# Microcontroller_IO.net
KiCad netlist of a schematic drawn in Altium Designer
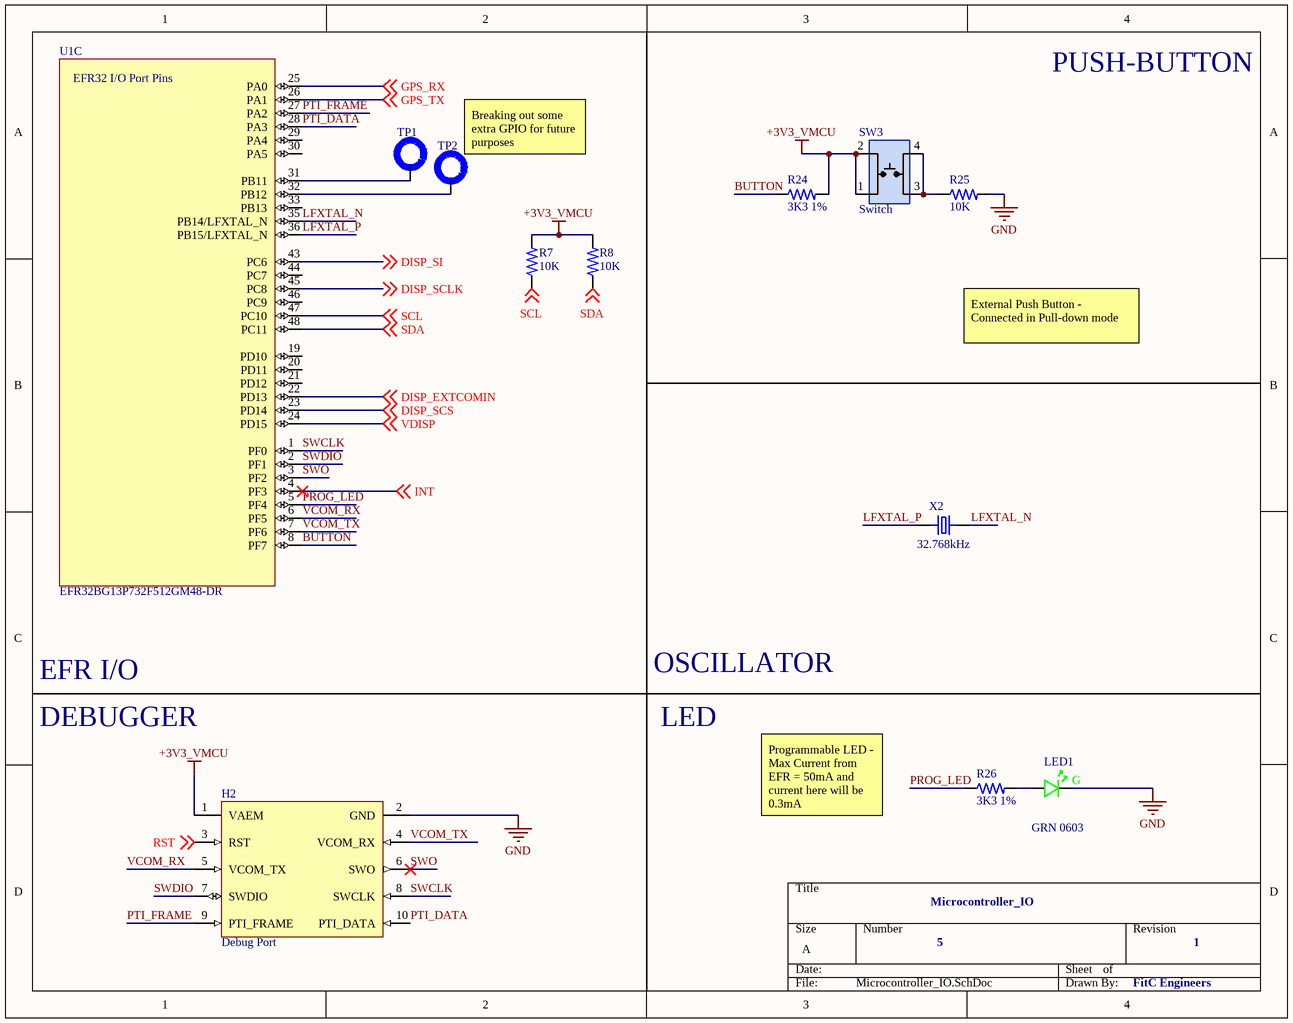
[diagram p0: Microcontroller_IO.SchDoc]

(export (version "E")
  (design (tool "Eeschema 10.0.6"))
  (components
    (comp (ref "H2")
      (value "Debug Port")
      (footprint "Amphenol_20021121_0")
      (description "CONN HEADER SMD 10POS 1.27MM. Connector Header Surface Mount 10 position 0.050\"")
      (fields
        (field (name "MANUFACTURER") "Amphenol ICC / FCI")
        (field (name "MANUFACTURER PART NUMBER") "20021121-00010C1LF")
      )
      (libsource (lib "LP_Project_Parts") (part "20021121-00010C1LF"))
    )
    (comp (ref "LED1")
      (value "GRN 0603")
      (footprint "LED_0603_GRN_WL-SMCW")
      (description "LED, 0603, GREEN, 430MCD, 520NM")
      (fields
        (field (name "MANUFACTURER") "Wurth Electronics")
        (field (name "MANUFACTURER PART NUMBER") "150060GS75000")
      )
      (libsource (lib "LP_Project_Parts") (part "150060GS75000"))
    )
    (comp (ref "R7")
      (value "10K")
      (footprint "RES_0603_1608X06")
      (description "Res Thin Film 0603 10K Ohm 1% 1/8W ±100ppm/°C Molded SMD SMD Paper T/R")
      (fields
        (field (name "MANUFACTURER") "Stackpole Electronics")
        (field (name "MANUFACTURER PART NUMBER") "RNCP0603FTD10K0")
      )
      (libsource (lib "LP_Project_Parts") (part "RNCP0603FTD10K0"))
    )
    (comp (ref "R8")
      (value "10K")
      (footprint "RES_0603_1608X06")
      (description "Res Thin Film 0603 10K Ohm 1% 1/8W ±100ppm/°C Molded SMD SMD Paper T/R")
      (fields
        (field (name "MANUFACTURER") "Stackpole Electronics")
        (field (name "MANUFACTURER PART NUMBER") "RNCP0603FTD10K0")
      )
      (libsource (lib "LP_Project_Parts") (part "RNCP0603FTD10K0"))
    )
    (comp (ref "R24")
      (value "3K3 1%")
      (footprint "RES_0603_1608X06")
      (description "Res Thick Film 0603 3.3K Ohm 1% 0.1W(1/10W) ±100ppm/C Pad SMD Automotive T/R")
      (fields
        (field (name "MANUFACTURER") "Stackpole Electronics")
        (field (name "MANUFACTURER PART NUMBER") "RMCF0603FT3K30")
      )
      (libsource (lib "LP_Project_Parts") (part "RMCF0603FT3K30"))
    )
    (comp (ref "R25")
      (value "10K")
      (footprint "RES_0603_1608X06")
      (description "Res Thin Film 0603 10K Ohm 1% 1/8W ±100ppm/°C Molded SMD SMD Paper T/R")
      (fields
        (field (name "MANUFACTURER") "Stackpole Electronics")
        (field (name "MANUFACTURER PART NUMBER") "RNCP0603FTD10K0")
      )
      (libsource (lib "LP_Project_Parts") (part "RNCP0603FTD10K0"))
    )
    (comp (ref "R26")
      (value "3K3 1%")
      (footprint "RES_0603_1608X06")
      (description "Res Thick Film 0603 3.3K Ohm 1% 0.1W(1/10W) ±100ppm/C Pad SMD Automotive T/R")
      (fields
        (field (name "MANUFACTURER") "Stackpole Electronics")
        (field (name "MANUFACTURER PART NUMBER") "RMCF0603FT3K30")
      )
      (libsource (lib "LP_Project_Parts") (part "RMCF0603FT3K30"))
    )
    (comp (ref "SW3")
      (value "Switch")
      (footprint "SWITCH")
      (description "Switch Tactile SPST-NO Button Gull Wing 50mA 12VDC 100000Cycle 180gf Surface Mount T/R")
      (fields
        (field (name "MANUFACTURER") "C&K Components")
        (field (name "MANUFACTURER PART NUMBER") "RKB2SJM250SMTR LFS")
      )
      (libsource (lib "LP_Project_Parts") (part "RKB2SJM250SMTR LFS (2)"))
    )
    (comp (ref "TP1")
      (value "Test Pad for Testing")
      (footprint "1mm Test Pad")
      (libsource (lib "LP_Project_Parts") (part "Test_Pad"))
    )
    (comp (ref "TP2")
      (value "Test Pad for Testing")
      (footprint "1mm Test Pad")
      (libsource (lib "LP_Project_Parts") (part "Test_Pad"))
    )
    (comp (ref "U1")
      (value "EFR32BG13P732F512GM48-DR")
      (footprint "EFR32BG13_48_QFN")
      (description "Blue Gecko QFN48 2.4 G 19 dB BLE/Proprietary 512 kB 64 kB(RAM) 31GPIO")
      (fields (field (name "MANUFACTURER") "Silicon Labs"))
      (libsource (lib "LP_Project_Parts") (part "EFR32BG13P732F512GM48-DR"))
    )
    (comp (ref "X2")
      (value "32.768kHz")
      (footprint "XTAL_ECS-.327-7-34B-TR")
      (description "32.768kHz Â±20ppm Crystal 7pF 70 kOhms 2-SMD, No Lead")
      (fields (field (name "MP") "ECS-.327-7-34B-TR") (field (name "MF") "ECS Inc."))
      (libsource (lib "LP_Project_Parts") (part "ECS-.327-7-34B-TR"))
    )
  )
  (nets
    (net (code "1") (name "+3V3_VMCU") (class "Default")
      (node (ref "H2") (pin "1") (pinfunction "VAEM_1") (pintype "power_in"))
      (node (ref "R24") (pin "2") (pinfunction "2_2") (pintype "passive"))
      (node (ref "R7") (pin "2") (pinfunction "2_2") (pintype "passive"))
      (node (ref "R8") (pin "2") (pinfunction "2_2") (pintype "passive"))
      (node (ref "SW3") (pin "1") (pinfunction "1_1") (pintype "passive"))
      (node (ref "SW3") (pin "2") (pinfunction "2_2") (pintype "passive"))
    )
    (net (code "2") (name "/BUTTON") (class "Default")
      (node (ref "R24") (pin "1") (pinfunction "1_1") (pintype "passive"))
      (node (ref "U1") (pin "8") (pinfunction "PF7_8") (pintype "bidirectional"))
    )
    (net (code "3") (name "/LFXTAL_N") (class "Default")
      (node (ref "U1") (pin "35") (pinfunction "PB14/LFXTAL_N_35") (pintype "bidirectional"))
      (node (ref "X2") (pin "2") (pinfunction "2_2") (pintype "passive"))
    )
    (net (code "4") (name "/LFXTAL_P") (class "Default")
      (node (ref "U1") (pin "36") (pinfunction "PB15/LFXTAL_N_36") (pintype "bidirectional"))
      (node (ref "X2") (pin "1") (pinfunction "1_1") (pintype "passive"))
    )
    (net (code "5") (name "/PROG_LED") (class "Default")
      (node (ref "R26") (pin "1") (pinfunction "1_1") (pintype "passive"))
      (node (ref "U1") (pin "5") (pinfunction "PF4_5") (pintype "bidirectional"))
    )
    (net (code "6") (name "/PTI_DATA") (class "Default")
      (node (ref "H2") (pin "10") (pinfunction "PTI_DATA_10") (pintype "input"))
      (node (ref "U1") (pin "28") (pinfunction "PA3_28") (pintype "bidirectional"))
    )
    (net (code "7") (name "/PTI_FRAME") (class "Default")
      (node (ref "H2") (pin "9") (pinfunction "PTI_FRAME_9") (pintype "input"))
      (node (ref "U1") (pin "27") (pinfunction "PA2_27") (pintype "bidirectional"))
    )
    (net (code "8") (name "/SWCLK") (class "Default")
      (node (ref "H2") (pin "8") (pinfunction "SWCLK_8") (pintype "input"))
      (node (ref "U1") (pin "1") (pinfunction "PF0_1") (pintype "bidirectional"))
    )
    (net (code "9") (name "/SWDIO") (class "Default")
      (node (ref "H2") (pin "7") (pinfunction "SWDIO_7") (pintype "bidirectional"))
      (node (ref "U1") (pin "2") (pinfunction "PF1_2") (pintype "bidirectional"))
    )
    (net (code "10") (name "/SWO") (class "Default")
      (node (ref "H2") (pin "6") (pinfunction "SWO_6") (pintype "output"))
      (node (ref "U1") (pin "3") (pinfunction "PF2_3") (pintype "bidirectional"))
    )
    (net (code "11") (name "/VCOM_RX") (class "Default")
      (node (ref "H2") (pin "5") (pinfunction "VCOM_TX_5") (pintype "input"))
      (node (ref "U1") (pin "6") (pinfunction "PF5_6") (pintype "bidirectional"))
    )
    (net (code "12") (name "/VCOM_TX") (class "Default")
      (node (ref "H2") (pin "4") (pinfunction "VCOM_RX_4") (pintype "input"))
      (node (ref "U1") (pin "7") (pinfunction "PF6_7") (pintype "bidirectional"))
    )
    (net (code "13") (name "DISP_EXTCOMIN") (class "Default")
      (node (ref "U1") (pin "22") (pinfunction "PD13_22") (pintype "bidirectional"))
    )
    (net (code "14") (name "DISP_SCLK") (class "Default")
      (node (ref "U1") (pin "45") (pinfunction "PC8_45") (pintype "bidirectional"))
    )
    (net (code "15") (name "DISP_SCS") (class "Default")
      (node (ref "U1") (pin "23") (pinfunction "PD14_23") (pintype "bidirectional"))
    )
    (net (code "16") (name "DISP_SI") (class "Default")
      (node (ref "U1") (pin "43") (pinfunction "PC6_43") (pintype "bidirectional"))
    )
    (net (code "17") (name "GND") (class "Default")
      (node (ref "H2") (pin "2") (pinfunction "GND_2") (pintype "power_in"))
      (node (ref "LED1") (pin "C") (pinfunction "C_C") (pintype "passive"))
      (node (ref "R25") (pin "2") (pinfunction "2_2") (pintype "passive"))
    )
    (net (code "18") (name "GPS_RX") (class "Default")
      (node (ref "U1") (pin "25") (pinfunction "PA0_25") (pintype "bidirectional"))
    )
    (net (code "19") (name "GPS_TX") (class "Default")
      (node (ref "U1") (pin "26") (pinfunction "PA1_26") (pintype "bidirectional"))
    )
    (net (code "20") (name "INT") (class "Default")
      (node (ref "U1") (pin "4") (pinfunction "PF3_4") (pintype "bidirectional"))
    )
    (net (code "21") (name "Net-(LED1-PadA)") (class "Default")
      (node (ref "LED1") (pin "A") (pinfunction "A_A") (pintype "passive"))
      (node (ref "R26") (pin "2") (pinfunction "2_2") (pintype "passive"))
    )
    (net (code "22") (name "Net-(R25-Pad1)") (class "Default")
      (node (ref "R25") (pin "1") (pinfunction "1_1") (pintype "passive"))
      (node (ref "SW3") (pin "3") (pinfunction "3_3") (pintype "passive"))
      (node (ref "SW3") (pin "4") (pinfunction "4_4") (pintype "passive"))
    )
    (net (code "23") (name "Net-(U1C-PB11)") (class "Default")
      (node (ref "TP1") (pin "1") (pinfunction "1_1") (pintype "passive"))
      (node (ref "U1") (pin "31") (pinfunction "PB11_31") (pintype "bidirectional"))
    )
    (net (code "24") (name "Net-(U1C-PB12)") (class "Default")
      (node (ref "TP2") (pin "1") (pinfunction "1_1") (pintype "passive"))
      (node (ref "U1") (pin "32") (pinfunction "PB12_32") (pintype "bidirectional"))
    )
    (net (code "25") (name "RST") (class "Default")
      (node (ref "H2") (pin "3") (pinfunction "RST_3") (pintype "input"))
    )
    (net (code "26") (name "SCL") (class "Default")
      (node (ref "R7") (pin "1") (pinfunction "1_1") (pintype "passive"))
      (node (ref "U1") (pin "47") (pinfunction "PC10_47") (pintype "bidirectional"))
    )
    (net (code "27") (name "SDA") (class "Default")
      (node (ref "R8") (pin "1") (pinfunction "1_1") (pintype "passive"))
      (node (ref "U1") (pin "48") (pinfunction "PC11_48") (pintype "bidirectional"))
    )
    (net (code "28") (name "VDISP") (class "Default")
      (node (ref "U1") (pin "24") (pinfunction "PD15_24") (pintype "bidirectional"))
    )
    (net (code "29") (name "unconnected-(U1C-PA4-Pad29)") (class "Default")
      (node (ref "U1") (pin "29") (pinfunction "PA4_29") (pintype "bidirectional"))
    )
    (net (code "30") (name "unconnected-(U1C-PA5-Pad30)") (class "Default")
      (node (ref "U1") (pin "30") (pinfunction "PA5_30") (pintype "bidirectional"))
    )
    (net (code "31") (name "unconnected-(U1C-PB13-Pad33)") (class "Default")
      (node (ref "U1") (pin "33") (pinfunction "PB13_33") (pintype "bidirectional"))
    )
    (net (code "32") (name "unconnected-(U1C-PC7-Pad44)") (class "Default")
      (node (ref "U1") (pin "44") (pinfunction "PC7_44") (pintype "bidirectional"))
    )
    (net (code "33") (name "unconnected-(U1C-PC9-Pad46)") (class "Default")
      (node (ref "U1") (pin "46") (pinfunction "PC9_46") (pintype "bidirectional"))
    )
    (net (code "34") (name "unconnected-(U1C-PD10-Pad19)") (class "Default")
      (node (ref "U1") (pin "19") (pinfunction "PD10_19") (pintype "bidirectional"))
    )
    (net (code "35") (name "unconnected-(U1C-PD11-Pad20)") (class "Default")
      (node (ref "U1") (pin "20") (pinfunction "PD11_20") (pintype "bidirectional"))
    )
    (net (code "36") (name "unconnected-(U1C-PD12-Pad21)") (class "Default")
      (node (ref "U1") (pin "21") (pinfunction "PD12_21") (pintype "bidirectional"))
    )
  )
)
